# 14-FPGA-01a.net
KiCad netlist of a schematic drawn in Altium Designer
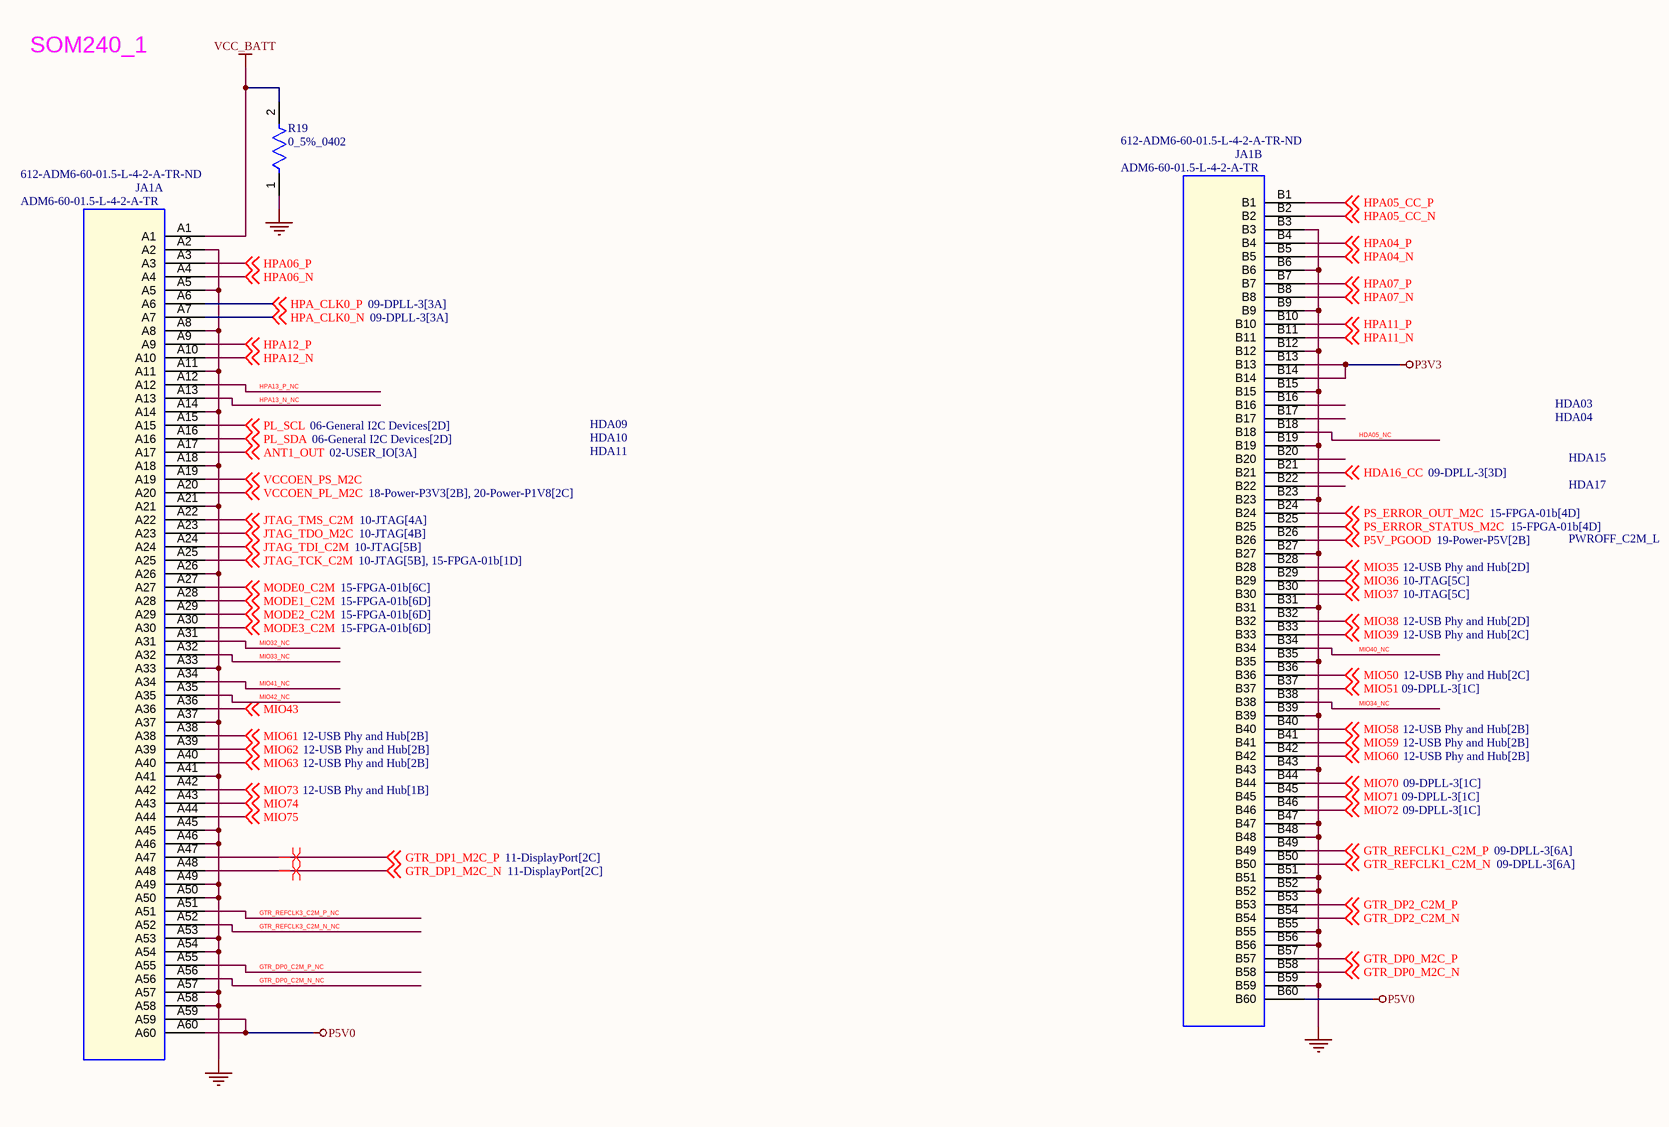
[diagram p0: 14-FPGA-01a.SchDoc]

(export (version "E")
  (design (tool "Eeschema 10.0.6"))
  (components
    (comp (ref "JA1")
      (value "ADM6-60-01.5-L-4-2-A-TR")
      (footprint "CON_SAMTEC_ADM6_60_4")
      (description "Conn Rcpt Male Vert 240 Pos 4x60 0.635mm P Black SMT")
      (fields
        (field (name "MANUFACTURER") "Samtec Inc.")
        (field (name "AGILE PART NUMBER") "CON-00383-01")
        (field (name "SUPPLIER PART NUMBER 1") "612-ADM6-60-01.5-L-4-2-A-TR-ND")
      )
      (libsource (lib "*") (part "SAMTEC-ADx6-60X4"))
    )
    (comp (ref "R19")
      (value "0_5%_0402")
      (footprint "FP-AC0402-0_37-IPC_B")
      (description "RESISTOR 0402 JUMPER ZERO OHM")
      (fields (field (name "TOLERANCE") "1%"))
      (libsource (lib "Altium Content Vault") (part "1029c3af85768c4190bb7ad29bc67b5"))
    )
  )
  (nets
    (net (code "1") (name "/GTR_DP0_C2M_N_NC") (class "Default")
      (node (ref "JA1") (pin "A56") (pinfunction "A56_A56") (pintype "passive"))
    )
    (net (code "2") (name "/GTR_DP0_C2M_P_NC") (class "Default")
      (node (ref "JA1") (pin "A55") (pinfunction "A55_A55") (pintype "passive"))
    )
    (net (code "3") (name "/GTR_REFCLK3_C2M_N_NC") (class "Default")
      (node (ref "JA1") (pin "A52") (pinfunction "A52_A52") (pintype "passive"))
    )
    (net (code "4") (name "/GTR_REFCLK3_C2M_P_NC") (class "Default")
      (node (ref "JA1") (pin "A51") (pinfunction "A51_A51") (pintype "passive"))
    )
    (net (code "5") (name "/HDA05_NC") (class "Default")
      (node (ref "JA1") (pin "B18") (pinfunction "B18_B18") (pintype "passive"))
    )
    (net (code "6") (name "/HPA13_N_NC") (class "Default")
      (node (ref "JA1") (pin "A13") (pinfunction "A13_A13") (pintype "passive"))
    )
    (net (code "7") (name "/HPA13_P_NC") (class "Default")
      (node (ref "JA1") (pin "A12") (pinfunction "A12_A12") (pintype "passive"))
    )
    (net (code "8") (name "/MIO32_NC") (class "Default")
      (node (ref "JA1") (pin "A31") (pinfunction "A31_A31") (pintype "passive"))
    )
    (net (code "9") (name "/MIO33_NC") (class "Default")
      (node (ref "JA1") (pin "A32") (pinfunction "A32_A32") (pintype "passive"))
    )
    (net (code "10") (name "/MIO34_NC") (class "Default")
      (node (ref "JA1") (pin "B38") (pinfunction "B38_B38") (pintype "passive"))
    )
    (net (code "11") (name "/MIO40_NC") (class "Default")
      (node (ref "JA1") (pin "B34") (pinfunction "B34_B34") (pintype "passive"))
    )
    (net (code "12") (name "/MIO41_NC") (class "Default")
      (node (ref "JA1") (pin "A34") (pinfunction "A34_A34") (pintype "passive"))
    )
    (net (code "13") (name "/MIO42_NC") (class "Default")
      (node (ref "JA1") (pin "A35") (pinfunction "A35_A35") (pintype "passive"))
    )
    (net (code "14") (name "ANT1_OUT") (class "Default")
      (node (ref "JA1") (pin "A17") (pinfunction "A17_A17") (pintype "passive"))
    )
    (net (code "15") (name "GND") (class "Default")
      (node (ref "JA1") (pin "A11") (pinfunction "A11_A11") (pintype "passive"))
      (node (ref "JA1") (pin "A14") (pinfunction "A14_A14") (pintype "passive"))
      (node (ref "JA1") (pin "A18") (pinfunction "A18_A18") (pintype "passive"))
      (node (ref "JA1") (pin "A2") (pinfunction "A2_A2") (pintype "passive"))
      (node (ref "JA1") (pin "A21") (pinfunction "A21_A21") (pintype "passive"))
      (node (ref "JA1") (pin "A26") (pinfunction "A26_A26") (pintype "passive"))
      (node (ref "JA1") (pin "A33") (pinfunction "A33_A33") (pintype "passive"))
      (node (ref "JA1") (pin "A37") (pinfunction "A37_A37") (pintype "passive"))
      (node (ref "JA1") (pin "A41") (pinfunction "A41_A41") (pintype "passive"))
      (node (ref "JA1") (pin "A45") (pinfunction "A45_A45") (pintype "passive"))
      (node (ref "JA1") (pin "A46") (pinfunction "A46_A46") (pintype "passive"))
      (node (ref "JA1") (pin "A49") (pinfunction "A49_A49") (pintype "passive"))
      (node (ref "JA1") (pin "A5") (pinfunction "A5_A5") (pintype "passive"))
      (node (ref "JA1") (pin "A50") (pinfunction "A50_A50") (pintype "passive"))
      (node (ref "JA1") (pin "A53") (pinfunction "A53_A53") (pintype "passive"))
      (node (ref "JA1") (pin "A54") (pinfunction "A54_A54") (pintype "passive"))
      (node (ref "JA1") (pin "A57") (pinfunction "A57_A57") (pintype "passive"))
      (node (ref "JA1") (pin "A58") (pinfunction "A58_A58") (pintype "passive"))
      (node (ref "JA1") (pin "A8") (pinfunction "A8_A8") (pintype "passive"))
      (node (ref "JA1") (pin "B12") (pinfunction "B12_B12") (pintype "passive"))
      (node (ref "JA1") (pin "B15") (pinfunction "B15_B15") (pintype "passive"))
      (node (ref "JA1") (pin "B19") (pinfunction "B19_B19") (pintype "passive"))
      (node (ref "JA1") (pin "B23") (pinfunction "B23_B23") (pintype "passive"))
      (node (ref "JA1") (pin "B27") (pinfunction "B27_B27") (pintype "passive"))
      (node (ref "JA1") (pin "B3") (pinfunction "B3_B3") (pintype "passive"))
      (node (ref "JA1") (pin "B31") (pinfunction "B31_B31") (pintype "passive"))
      (node (ref "JA1") (pin "B35") (pinfunction "B35_B35") (pintype "passive"))
      (node (ref "JA1") (pin "B39") (pinfunction "B39_B39") (pintype "passive"))
      (node (ref "JA1") (pin "B43") (pinfunction "B43_B43") (pintype "passive"))
      (node (ref "JA1") (pin "B47") (pinfunction "B47_B47") (pintype "passive"))
      (node (ref "JA1") (pin "B48") (pinfunction "B48_B48") (pintype "passive"))
      (node (ref "JA1") (pin "B51") (pinfunction "B51_B51") (pintype "passive"))
      (node (ref "JA1") (pin "B52") (pinfunction "B52_B52") (pintype "passive"))
      (node (ref "JA1") (pin "B55") (pinfunction "B55_B55") (pintype "passive"))
      (node (ref "JA1") (pin "B56") (pinfunction "B56_B56") (pintype "passive"))
      (node (ref "JA1") (pin "B59") (pinfunction "B59_B59") (pintype "passive"))
      (node (ref "JA1") (pin "B6") (pinfunction "B6_B6") (pintype "passive"))
      (node (ref "JA1") (pin "B9") (pinfunction "B9_B9") (pintype "passive"))
      (node (ref "R19") (pin "1") (pinfunction "1_1") (pintype "passive"))
    )
    (net (code "16") (name "GTR_DP0_M2C_N") (class "Default")
      (node (ref "JA1") (pin "B58") (pinfunction "B58_B58") (pintype "passive"))
    )
    (net (code "17") (name "GTR_DP0_M2C_P") (class "Default")
      (node (ref "JA1") (pin "B57") (pinfunction "B57_B57") (pintype "passive"))
    )
    (net (code "18") (name "GTR_DP1_M2C_N") (class "Default")
      (node (ref "JA1") (pin "A48") (pinfunction "A48_A48") (pintype "passive"))
    )
    (net (code "19") (name "GTR_DP1_M2C_P") (class "Default")
      (node (ref "JA1") (pin "A47") (pinfunction "A47_A47") (pintype "passive"))
    )
    (net (code "20") (name "GTR_DP2_C2M_N") (class "Default")
      (node (ref "JA1") (pin "B54") (pinfunction "B54_B54") (pintype "passive"))
    )
    (net (code "21") (name "GTR_DP2_C2M_P") (class "Default")
      (node (ref "JA1") (pin "B53") (pinfunction "B53_B53") (pintype "passive"))
    )
    (net (code "22") (name "GTR_REFCLK1_C2M_N") (class "Default")
      (node (ref "JA1") (pin "B50") (pinfunction "B50_B50") (pintype "passive"))
    )
    (net (code "23") (name "GTR_REFCLK1_C2M_P") (class "Default")
      (node (ref "JA1") (pin "B49") (pinfunction "B49_B49") (pintype "passive"))
    )
    (net (code "24") (name "HDA16_CC") (class "Default")
      (node (ref "JA1") (pin "B21") (pinfunction "B21_B21") (pintype "passive"))
    )
    (net (code "25") (name "HPA04_N") (class "Default")
      (node (ref "JA1") (pin "B5") (pinfunction "B5_B5") (pintype "passive"))
    )
    (net (code "26") (name "HPA04_P") (class "Default")
      (node (ref "JA1") (pin "B4") (pinfunction "B4_B4") (pintype "passive"))
    )
    (net (code "27") (name "HPA05_CC_N") (class "Default")
      (node (ref "JA1") (pin "B2") (pinfunction "B2_B2") (pintype "passive"))
    )
    (net (code "28") (name "HPA05_CC_P") (class "Default")
      (node (ref "JA1") (pin "B1") (pinfunction "B1_B1") (pintype "passive"))
    )
    (net (code "29") (name "HPA06_N") (class "Default")
      (node (ref "JA1") (pin "A4") (pinfunction "A4_A4") (pintype "passive"))
    )
    (net (code "30") (name "HPA06_P") (class "Default")
      (node (ref "JA1") (pin "A3") (pinfunction "A3_A3") (pintype "passive"))
    )
    (net (code "31") (name "HPA07_N") (class "Default")
      (node (ref "JA1") (pin "B8") (pinfunction "B8_B8") (pintype "passive"))
    )
    (net (code "32") (name "HPA07_P") (class "Default")
      (node (ref "JA1") (pin "B7") (pinfunction "B7_B7") (pintype "passive"))
    )
    (net (code "33") (name "HPA11_N") (class "Default")
      (node (ref "JA1") (pin "B11") (pinfunction "B11_B11") (pintype "passive"))
    )
    (net (code "34") (name "HPA11_P") (class "Default")
      (node (ref "JA1") (pin "B10") (pinfunction "B10_B10") (pintype "passive"))
    )
    (net (code "35") (name "HPA12_N") (class "Default")
      (node (ref "JA1") (pin "A10") (pinfunction "A10_A10") (pintype "passive"))
    )
    (net (code "36") (name "HPA12_P") (class "Default")
      (node (ref "JA1") (pin "A9") (pinfunction "A9_A9") (pintype "passive"))
    )
    (net (code "37") (name "HPA_CLK0_N") (class "Default")
      (node (ref "JA1") (pin "A7") (pinfunction "A7_A7") (pintype "passive"))
    )
    (net (code "38") (name "HPA_CLK0_P") (class "Default")
      (node (ref "JA1") (pin "A6") (pinfunction "A6_A6") (pintype "passive"))
    )
    (net (code "39") (name "JTAG_TCK_C2M") (class "Default")
      (node (ref "JA1") (pin "A25") (pinfunction "A25_A25") (pintype "passive"))
    )
    (net (code "40") (name "JTAG_TDI_C2M") (class "Default")
      (node (ref "JA1") (pin "A24") (pinfunction "A24_A24") (pintype "passive"))
    )
    (net (code "41") (name "JTAG_TDO_M2C") (class "Default")
      (node (ref "JA1") (pin "A23") (pinfunction "A23_A23") (pintype "passive"))
    )
    (net (code "42") (name "JTAG_TMS_C2M") (class "Default")
      (node (ref "JA1") (pin "A22") (pinfunction "A22_A22") (pintype "passive"))
    )
    (net (code "43") (name "MIO35") (class "Default")
      (node (ref "JA1") (pin "B28") (pinfunction "B28_B28") (pintype "passive"))
    )
    (net (code "44") (name "MIO36") (class "Default")
      (node (ref "JA1") (pin "B29") (pinfunction "B29_B29") (pintype "passive"))
    )
    (net (code "45") (name "MIO37") (class "Default")
      (node (ref "JA1") (pin "B30") (pinfunction "B30_B30") (pintype "passive"))
    )
    (net (code "46") (name "MIO38") (class "Default")
      (node (ref "JA1") (pin "B32") (pinfunction "B32_B32") (pintype "passive"))
    )
    (net (code "47") (name "MIO39") (class "Default")
      (node (ref "JA1") (pin "B33") (pinfunction "B33_B33") (pintype "passive"))
    )
    (net (code "48") (name "MIO43") (class "Default")
      (node (ref "JA1") (pin "A36") (pinfunction "A36_A36") (pintype "passive"))
    )
    (net (code "49") (name "MIO50") (class "Default")
      (node (ref "JA1") (pin "B36") (pinfunction "B36_B36") (pintype "passive"))
    )
    (net (code "50") (name "MIO51") (class "Default")
      (node (ref "JA1") (pin "B37") (pinfunction "B37_B37") (pintype "passive"))
    )
    (net (code "51") (name "MIO58") (class "Default")
      (node (ref "JA1") (pin "B40") (pinfunction "B40_B40") (pintype "passive"))
    )
    (net (code "52") (name "MIO59") (class "Default")
      (node (ref "JA1") (pin "B41") (pinfunction "B41_B41") (pintype "passive"))
    )
    (net (code "53") (name "MIO60") (class "Default")
      (node (ref "JA1") (pin "B42") (pinfunction "B42_B42") (pintype "passive"))
    )
    (net (code "54") (name "MIO61") (class "Default")
      (node (ref "JA1") (pin "A38") (pinfunction "A38_A38") (pintype "passive"))
    )
    (net (code "55") (name "MIO62") (class "Default")
      (node (ref "JA1") (pin "A39") (pinfunction "A39_A39") (pintype "passive"))
    )
    (net (code "56") (name "MIO63") (class "Default")
      (node (ref "JA1") (pin "A40") (pinfunction "A40_A40") (pintype "passive"))
    )
    (net (code "57") (name "MIO70") (class "Default")
      (node (ref "JA1") (pin "B44") (pinfunction "B44_B44") (pintype "passive"))
    )
    (net (code "58") (name "MIO71") (class "Default")
      (node (ref "JA1") (pin "B45") (pinfunction "B45_B45") (pintype "passive"))
    )
    (net (code "59") (name "MIO72") (class "Default")
      (node (ref "JA1") (pin "B46") (pinfunction "B46_B46") (pintype "passive"))
    )
    (net (code "60") (name "MIO73") (class "Default")
      (node (ref "JA1") (pin "A42") (pinfunction "A42_A42") (pintype "passive"))
    )
    (net (code "61") (name "MIO74") (class "Default")
      (node (ref "JA1") (pin "A43") (pinfunction "A43_A43") (pintype "passive"))
    )
    (net (code "62") (name "MIO75") (class "Default")
      (node (ref "JA1") (pin "A44") (pinfunction "A44_A44") (pintype "passive"))
    )
    (net (code "63") (name "MODE0_C2M") (class "Default")
      (node (ref "JA1") (pin "A27") (pinfunction "A27_A27") (pintype "passive"))
    )
    (net (code "64") (name "MODE1_C2M") (class "Default")
      (node (ref "JA1") (pin "A28") (pinfunction "A28_A28") (pintype "passive"))
    )
    (net (code "65") (name "MODE2_C2M") (class "Default")
      (node (ref "JA1") (pin "A29") (pinfunction "A29_A29") (pintype "passive"))
    )
    (net (code "66") (name "MODE3_C2M") (class "Default")
      (node (ref "JA1") (pin "A30") (pinfunction "A30_A30") (pintype "passive"))
    )
    (net (code "67") (name "P3V3") (class "Default")
      (node (ref "JA1") (pin "B13") (pinfunction "B13_B13") (pintype "passive"))
      (node (ref "JA1") (pin "B14") (pinfunction "B14_B14") (pintype "passive"))
    )
    (net (code "68") (name "P5V0") (class "Default")
      (node (ref "JA1") (pin "A59") (pinfunction "A59_A59") (pintype "passive"))
      (node (ref "JA1") (pin "A60") (pinfunction "A60_A60") (pintype "passive"))
      (node (ref "JA1") (pin "B60") (pinfunction "B60_B60") (pintype "passive"))
    )
    (net (code "69") (name "P5V_PGOOD") (class "Default")
      (node (ref "JA1") (pin "B26") (pinfunction "B26_B26") (pintype "passive"))
    )
    (net (code "70") (name "PL_SCL") (class "Default")
      (node (ref "JA1") (pin "A15") (pinfunction "A15_A15") (pintype "passive"))
    )
    (net (code "71") (name "PL_SDA") (class "Default")
      (node (ref "JA1") (pin "A16") (pinfunction "A16_A16") (pintype "passive"))
    )
    (net (code "72") (name "PS_ERROR_OUT_M2C") (class "Default")
      (node (ref "JA1") (pin "B24") (pinfunction "B24_B24") (pintype "passive"))
    )
    (net (code "73") (name "PS_ERROR_STATUS_M2C") (class "Default")
      (node (ref "JA1") (pin "B25") (pinfunction "B25_B25") (pintype "passive"))
    )
    (net (code "74") (name "VCCOEN_PL_M2C") (class "Default")
      (node (ref "JA1") (pin "A20") (pinfunction "A20_A20") (pintype "passive"))
    )
    (net (code "75") (name "VCCOEN_PS_M2C") (class "Default")
      (node (ref "JA1") (pin "A19") (pinfunction "A19_A19") (pintype "passive"))
    )
    (net (code "76") (name "VCC_BATT") (class "Default")
      (node (ref "JA1") (pin "A1") (pinfunction "A1_A1") (pintype "passive"))
      (node (ref "R19") (pin "2") (pinfunction "2_2") (pintype "passive"))
    )
    (net (code "77") (name "unconnected-(JA1-PadB16)") (class "Default")
      (node (ref "JA1") (pin "B16") (pinfunction "B16_B16") (pintype "passive"))
    )
    (net (code "78") (name "unconnected-(JA1-PadB17)") (class "Default")
      (node (ref "JA1") (pin "B17") (pinfunction "B17_B17") (pintype "passive"))
    )
    (net (code "79") (name "unconnected-(JA1-PadB20)") (class "Default")
      (node (ref "JA1") (pin "B20") (pinfunction "B20_B20") (pintype "passive"))
    )
    (net (code "80") (name "unconnected-(JA1-PadB22)") (class "Default")
      (node (ref "JA1") (pin "B22") (pinfunction "B22_B22") (pintype "passive"))
    )
  )
)
